# approg.net
KiCad netlist of a schematic drawn in EAGLE
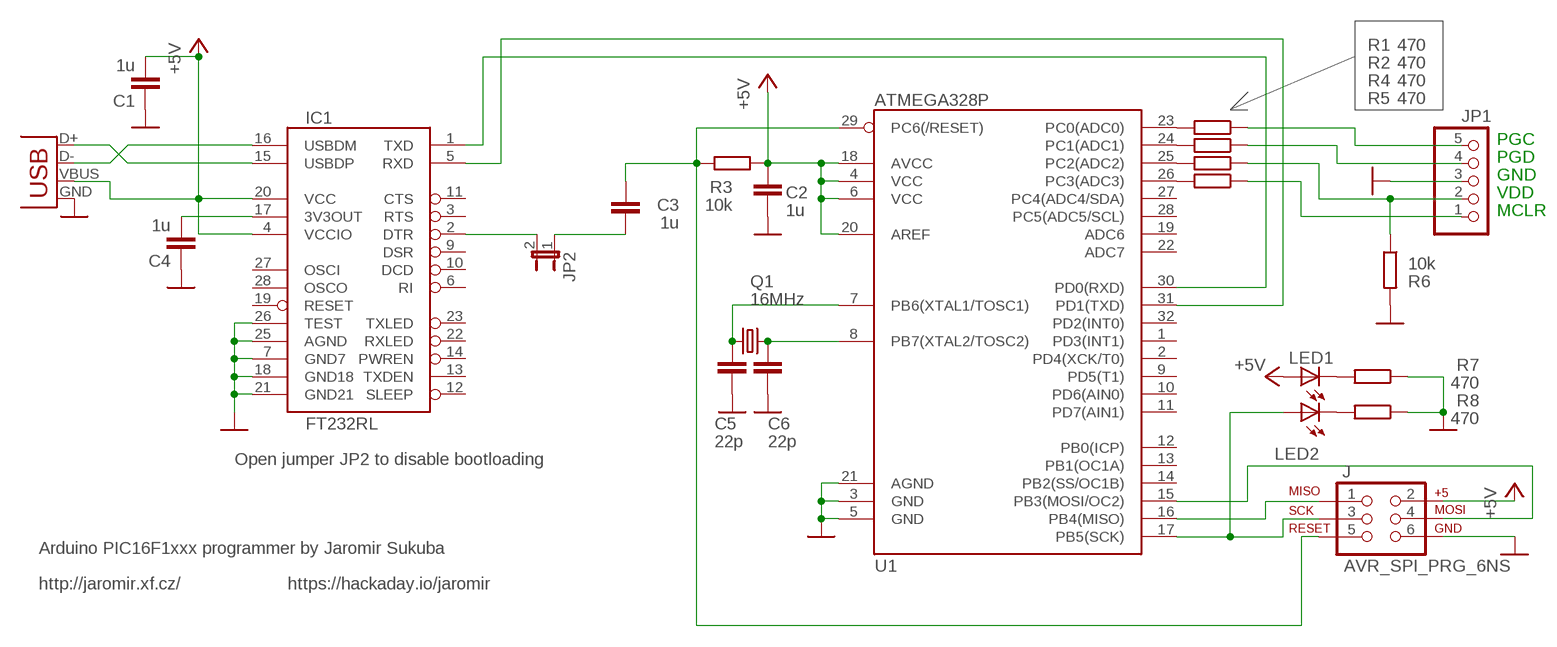
[diagram p0: schematic, sheet 1]

(export (version "E")
  (design (tool "Eeschema 10.0.6"))
  (components
    (comp (ref "C1")
      (value "1u")
      (footprint "eagle-import:R0805")
      (libsource (lib "eagle-import") (part "C_0806"))
    )
    (comp (ref "C2")
      (value "1u")
      (footprint "eagle-import:R0805")
      (libsource (lib "eagle-import") (part "C_0806"))
    )
    (comp (ref "C3")
      (value "1u")
      (footprint "eagle-import:R0805")
      (libsource (lib "eagle-import") (part "C_0806"))
    )
    (comp (ref "C4")
      (value "1u")
      (footprint "eagle-import:R0805")
      (libsource (lib "eagle-import") (part "C_0806"))
    )
    (comp (ref "C5")
      (value "22p")
      (footprint "eagle-import:R0805")
      (libsource (lib "eagle-import") (part "C_0806"))
    )
    (comp (ref "C6")
      (value "22p")
      (footprint "eagle-import:R0805")
      (libsource (lib "eagle-import") (part "C_0806"))
    )
    (comp (ref "IC1")
      (value "FT232RL")
      (footprint "eagle-import:SSOP28DB")
      (libsource (lib "eagle-import") (part "FT232RLSSOP"))
    )
    (comp (ref "J")
      (value "AVR_SPI_PRG_6NS")
      (footprint "eagle-import:2X3-NS")
      (libsource (lib "eagle-import") (part "AVR_SPI_PRG_6NS"))
    )
    (comp (ref "JP1")
      (value "PINHD-1X5/90")
      (footprint "eagle-import:1X05_90")
      (libsource (lib "eagle-import") (part "PINHD-1X5/90"))
    )
    (comp (ref "JP2")
      (value "JP1E")
      (footprint "eagle-import:JP1")
      (libsource (lib "eagle-import") (part "JP1E"))
    )
    (comp (ref "LED1")
      (value "LEDCHIPLED_0805")
      (footprint "eagle-import:CHIPLED_0805")
      (libsource (lib "eagle-import") (part "LEDCHIPLED_0805"))
    )
    (comp (ref "LED2")
      (value "LEDCHIPLED_0805")
      (footprint "eagle-import:CHIPLED_0805")
      (libsource (lib "eagle-import") (part "LEDCHIPLED_0805"))
    )
    (comp (ref "Q1")
      (value "16MHz")
      (footprint "eagle-import:HC49_S")
      (libsource (lib "eagle-import") (part "CRYSTALHC49S"))
    )
    (comp (ref "R1")
      (value "470")
      (footprint "eagle-import:R0805")
      (libsource (lib "eagle-import") (part "R_0805"))
    )
    (comp (ref "R2")
      (value "470")
      (footprint "eagle-import:R0805")
      (libsource (lib "eagle-import") (part "R_0805"))
    )
    (comp (ref "R3")
      (value "10k")
      (footprint "eagle-import:R0805")
      (libsource (lib "eagle-import") (part "R_0805"))
    )
    (comp (ref "R4")
      (value "470")
      (footprint "eagle-import:R0805")
      (libsource (lib "eagle-import") (part "R_0805"))
    )
    (comp (ref "R5")
      (value "470")
      (footprint "eagle-import:R0805")
      (libsource (lib "eagle-import") (part "R_0805"))
    )
    (comp (ref "R6")
      (value "10k")
      (footprint "eagle-import:R0805")
      (libsource (lib "eagle-import") (part "R_0805"))
    )
    (comp (ref "R7")
      (value "470")
      (footprint "eagle-import:R0805")
      (libsource (lib "eagle-import") (part "R_0805"))
    )
    (comp (ref "R8")
      (value "470")
      (footprint "eagle-import:R0805")
      (libsource (lib "eagle-import") (part "R_0805"))
    )
    (comp (ref "U1")
      (value "ATMEGA328P")
      (footprint "eagle-import:TQFP32-08")
      (libsource (lib "eagle-import") (part "ATMEGA328_SMT"))
    )
    (comp (ref "X1")
      (value "USB-MICROB")
      (footprint "eagle-import:USB-MICROB")
      (libsource (lib "eagle-import") (part "USB-MICROB"))
    )
  )
  (nets
    (net (code "1") (name "+5V") (class "Default")
      (node (ref "C1") (pin "2") (pinfunction "2_2") (pintype "passive"))
      (node (ref "C2") (pin "1") (pinfunction "1_1") (pintype "passive"))
      (node (ref "IC1") (pin "20") (pinfunction "VCC_20") (pintype "power_in"))
      (node (ref "IC1") (pin "4") (pinfunction "VCCIO_4") (pintype "power_in"))
      (node (ref "J") (pin "2") (pinfunction "2_2") (pintype "passive"))
      (node (ref "LED1") (pin "A") (pinfunction "A_A") (pintype "passive"))
      (node (ref "R3") (pin "1") (pinfunction "1_1") (pintype "passive"))
      (node (ref "U1") (pin "18") (pinfunction "AVCC_18") (pintype "bidirectional"))
      (node (ref "U1") (pin "20") (pinfunction "AREF_20") (pintype "bidirectional"))
      (node (ref "U1") (pin "4") (pinfunction "VCC_4") (pintype "bidirectional"))
      (node (ref "U1") (pin "6") (pinfunction "VCC_6") (pintype "bidirectional"))
      (node (ref "X1") (pin "VBUS") (pinfunction "VBUS_VBUS") (pintype "bidirectional"))
    )
    (net (code "2") (name "GND") (class "Default")
      (node (ref "C1") (pin "1") (pinfunction "1_1") (pintype "passive"))
      (node (ref "C2") (pin "2") (pinfunction "2_2") (pintype "passive"))
      (node (ref "C4") (pin "1") (pinfunction "1_1") (pintype "passive"))
      (node (ref "C5") (pin "2") (pinfunction "2_2") (pintype "passive"))
      (node (ref "C6") (pin "2") (pinfunction "2_2") (pintype "passive"))
      (node (ref "IC1") (pin "18") (pinfunction "GND18_18") (pintype "power_in"))
      (node (ref "IC1") (pin "21") (pinfunction "GND21_21") (pintype "power_in"))
      (node (ref "IC1") (pin "25") (pinfunction "AGND_25") (pintype "power_in"))
      (node (ref "IC1") (pin "26") (pinfunction "TEST_26") (pintype "input"))
      (node (ref "IC1") (pin "7") (pinfunction "GND7_7") (pintype "power_in"))
      (node (ref "J") (pin "6") (pinfunction "6_6") (pintype "passive"))
      (node (ref "JP1") (pin "3") (pinfunction "3_3") (pintype "passive"))
      (node (ref "R6") (pin "2") (pinfunction "2_2") (pintype "passive"))
      (node (ref "R7") (pin "1") (pinfunction "1_1") (pintype "passive"))
      (node (ref "R8") (pin "1") (pinfunction "1_1") (pintype "passive"))
      (node (ref "U1") (pin "21") (pinfunction "AGND_21") (pintype "bidirectional"))
      (node (ref "U1") (pin "3") (pinfunction "GND_3") (pintype "bidirectional"))
      (node (ref "U1") (pin "5") (pinfunction "GND_5") (pintype "bidirectional"))
      (node (ref "X1") (pin "GND") (pinfunction "GND_GND") (pintype "bidirectional"))
    )
    (net (code "3") (name "Net-(C3-Pad2)") (class "Default")
      (node (ref "C3") (pin "2") (pinfunction "2_2") (pintype "passive"))
      (node (ref "JP2") (pin "1") (pinfunction "1_1") (pintype "passive"))
    )
    (net (code "4") (name "Net-(IC1-3V3OUT)") (class "Default")
      (node (ref "C4") (pin "2") (pinfunction "2_2") (pintype "passive"))
      (node (ref "IC1") (pin "17") (pinfunction "3V3OUT_17") (pintype "output"))
    )
    (net (code "5") (name "Net-(IC1-DTR)") (class "Default")
      (node (ref "IC1") (pin "2") (pinfunction "DTR_2") (pintype "output"))
      (node (ref "JP2") (pin "2") (pinfunction "2_2") (pintype "passive"))
    )
    (net (code "6") (name "Net-(IC1-RXD)") (class "Default")
      (node (ref "IC1") (pin "5") (pinfunction "RXD_5") (pintype "input"))
      (node (ref "U1") (pin "31") (pinfunction "PD1(TXD)_31") (pintype "bidirectional"))
    )
    (net (code "7") (name "Net-(IC1-TXD)") (class "Default")
      (node (ref "IC1") (pin "1") (pinfunction "TXD_1") (pintype "output"))
      (node (ref "U1") (pin "30") (pinfunction "PD0(RXD)_30") (pintype "bidirectional"))
    )
    (net (code "8") (name "Net-(IC1-USBDM)") (class "Default")
      (node (ref "IC1") (pin "16") (pinfunction "USBDM_16") (pintype "bidirectional"))
      (node (ref "X1") (pin "D-") (pinfunction "D-_D-") (pintype "bidirectional"))
    )
    (net (code "9") (name "Net-(IC1-USBDP)") (class "Default")
      (node (ref "IC1") (pin "15") (pinfunction "USBDP_15") (pintype "bidirectional"))
      (node (ref "X1") (pin "D+") (pinfunction "D+_D+") (pintype "bidirectional"))
    )
    (net (code "10") (name "Net-(JP1-Pad1)") (class "Default")
      (node (ref "JP1") (pin "1") (pinfunction "1_1") (pintype "passive"))
      (node (ref "R5") (pin "1") (pinfunction "1_1") (pintype "passive"))
    )
    (net (code "11") (name "Net-(JP1-Pad2)") (class "Default")
      (node (ref "JP1") (pin "2") (pinfunction "2_2") (pintype "passive"))
      (node (ref "R4") (pin "1") (pinfunction "1_1") (pintype "passive"))
      (node (ref "R6") (pin "1") (pinfunction "1_1") (pintype "passive"))
    )
    (net (code "12") (name "Net-(JP1-Pad4)") (class "Default")
      (node (ref "JP1") (pin "4") (pinfunction "4_4") (pintype "passive"))
      (node (ref "R2") (pin "1") (pinfunction "1_1") (pintype "passive"))
    )
    (net (code "13") (name "Net-(JP1-Pad5)") (class "Default")
      (node (ref "JP1") (pin "5") (pinfunction "5_5") (pintype "passive"))
      (node (ref "R1") (pin "1") (pinfunction "1_1") (pintype "passive"))
    )
    (net (code "14") (name "Net-(LED1-PadC)") (class "Default")
      (node (ref "LED1") (pin "C") (pinfunction "C_C") (pintype "passive"))
      (node (ref "R7") (pin "2") (pinfunction "2_2") (pintype "passive"))
    )
    (net (code "15") (name "Net-(LED2-PadC)") (class "Default")
      (node (ref "LED2") (pin "C") (pinfunction "C_C") (pintype "passive"))
      (node (ref "R8") (pin "2") (pinfunction "2_2") (pintype "passive"))
    )
    (net (code "16") (name "Net-(U1-PB3(MOSI{slash}OC2))") (class "Default")
      (node (ref "J") (pin "4") (pinfunction "4_4") (pintype "passive"))
      (node (ref "U1") (pin "15") (pinfunction "PB3(MOSI/OC2)_15") (pintype "bidirectional"))
    )
    (net (code "17") (name "Net-(U1-PB4(MISO))") (class "Default")
      (node (ref "J") (pin "1") (pinfunction "1_1") (pintype "passive"))
      (node (ref "U1") (pin "16") (pinfunction "PB4(MISO)_16") (pintype "bidirectional"))
    )
    (net (code "18") (name "Net-(U1-PB5(SCK))") (class "Default")
      (node (ref "J") (pin "3") (pinfunction "3_3") (pintype "passive"))
      (node (ref "LED2") (pin "A") (pinfunction "A_A") (pintype "passive"))
      (node (ref "U1") (pin "17") (pinfunction "PB5(SCK)_17") (pintype "bidirectional"))
    )
    (net (code "19") (name "Net-(U1-PB6(XTAL1{slash}TOSC1))") (class "Default")
      (node (ref "C5") (pin "1") (pinfunction "1_1") (pintype "passive"))
      (node (ref "Q1") (pin "1") (pinfunction "1_1") (pintype "passive"))
      (node (ref "U1") (pin "7") (pinfunction "PB6(XTAL1/TOSC1)_7") (pintype "bidirectional"))
    )
    (net (code "20") (name "Net-(U1-PB7(XTAL2{slash}TOSC2))") (class "Default")
      (node (ref "C6") (pin "1") (pinfunction "1_1") (pintype "passive"))
      (node (ref "Q1") (pin "2") (pinfunction "2_2") (pintype "passive"))
      (node (ref "U1") (pin "8") (pinfunction "PB7(XTAL2/TOSC2)_8") (pintype "bidirectional"))
    )
    (net (code "21") (name "Net-(U1-PC0(ADC0))") (class "Default")
      (node (ref "R1") (pin "2") (pinfunction "2_2") (pintype "passive"))
      (node (ref "U1") (pin "23") (pinfunction "PC0(ADC0)_23") (pintype "bidirectional"))
    )
    (net (code "22") (name "Net-(U1-PC1(ADC1))") (class "Default")
      (node (ref "R2") (pin "2") (pinfunction "2_2") (pintype "passive"))
      (node (ref "U1") (pin "24") (pinfunction "PC1(ADC1)_24") (pintype "bidirectional"))
    )
    (net (code "23") (name "Net-(U1-PC2(ADC2))") (class "Default")
      (node (ref "R4") (pin "2") (pinfunction "2_2") (pintype "passive"))
      (node (ref "U1") (pin "25") (pinfunction "PC2(ADC2)_25") (pintype "bidirectional"))
    )
    (net (code "24") (name "Net-(U1-PC3(ADC3))") (class "Default")
      (node (ref "R5") (pin "2") (pinfunction "2_2") (pintype "passive"))
      (node (ref "U1") (pin "26") (pinfunction "PC3(ADC3)_26") (pintype "bidirectional"))
    )
    (net (code "25") (name "Net-(U1-PC6({slash}RESET))") (class "Default")
      (node (ref "C3") (pin "1") (pinfunction "1_1") (pintype "passive"))
      (node (ref "J") (pin "5") (pinfunction "5_5") (pintype "passive"))
      (node (ref "R3") (pin "2") (pinfunction "2_2") (pintype "passive"))
      (node (ref "U1") (pin "29") (pinfunction "PC6(/RESET)_29") (pintype "bidirectional"))
    )
    (net (code "26") (name "unconnected-(IC1-CTS-Pad11)") (class "Default")
      (node (ref "IC1") (pin "11") (pinfunction "CTS_11") (pintype "input"))
    )
    (net (code "27") (name "unconnected-(IC1-DCD-Pad10)") (class "Default")
      (node (ref "IC1") (pin "10") (pinfunction "DCD_10") (pintype "input"))
    )
    (net (code "28") (name "unconnected-(IC1-DSR-Pad9)") (class "Default")
      (node (ref "IC1") (pin "9") (pinfunction "DSR_9") (pintype "input"))
    )
    (net (code "29") (name "unconnected-(IC1-OSCI-Pad27)") (class "Default")
      (node (ref "IC1") (pin "27") (pinfunction "OSCI_27") (pintype "input"))
    )
    (net (code "30") (name "unconnected-(IC1-OSCO-Pad28)") (class "Default")
      (node (ref "IC1") (pin "28") (pinfunction "OSCO_28") (pintype "output"))
    )
    (net (code "31") (name "unconnected-(IC1-PWREN-Pad14)") (class "Default")
      (node (ref "IC1") (pin "14") (pinfunction "PWREN_14") (pintype "input"))
    )
    (net (code "32") (name "unconnected-(IC1-RESET-Pad19)") (class "Default")
      (node (ref "IC1") (pin "19") (pinfunction "RESET_19") (pintype "input"))
    )
    (net (code "33") (name "unconnected-(IC1-RI-Pad6)") (class "Default")
      (node (ref "IC1") (pin "6") (pinfunction "RI_6") (pintype "input"))
    )
    (net (code "34") (name "unconnected-(IC1-RTS-Pad3)") (class "Default")
      (node (ref "IC1") (pin "3") (pinfunction "RTS_3") (pintype "output"))
    )
    (net (code "35") (name "unconnected-(IC1-RXLED-Pad22)") (class "Default")
      (node (ref "IC1") (pin "22") (pinfunction "RXLED_22") (pintype "input"))
    )
    (net (code "36") (name "unconnected-(IC1-SLEEP-Pad12)") (class "Default")
      (node (ref "IC1") (pin "12") (pinfunction "SLEEP_12") (pintype "input"))
    )
    (net (code "37") (name "unconnected-(IC1-TXDEN-Pad13)") (class "Default")
      (node (ref "IC1") (pin "13") (pinfunction "TXDEN_13") (pintype "input"))
    )
    (net (code "38") (name "unconnected-(IC1-TXLED-Pad23)") (class "Default")
      (node (ref "IC1") (pin "23") (pinfunction "TXLED_23") (pintype "input"))
    )
    (net (code "39") (name "unconnected-(U1-ADC6-Pad19)") (class "Default")
      (node (ref "U1") (pin "19") (pinfunction "ADC6_19") (pintype "bidirectional"))
    )
    (net (code "40") (name "unconnected-(U1-ADC7-Pad22)") (class "Default")
      (node (ref "U1") (pin "22") (pinfunction "ADC7_22") (pintype "bidirectional"))
    )
    (net (code "41") (name "unconnected-(U1-PB0(ICP)-Pad12)") (class "Default")
      (node (ref "U1") (pin "12") (pinfunction "PB0(ICP)_12") (pintype "bidirectional"))
    )
    (net (code "42") (name "unconnected-(U1-PB1(OC1A)-Pad13)") (class "Default")
      (node (ref "U1") (pin "13") (pinfunction "PB1(OC1A)_13") (pintype "bidirectional"))
    )
    (net (code "43") (name "unconnected-(U1-PB2(SS{slash}OC1B)-Pad14)") (class "Default")
      (node (ref "U1") (pin "14") (pinfunction "PB2(SS/OC1B)_14") (pintype "bidirectional"))
    )
    (net (code "44") (name "unconnected-(U1-PC4(ADC4{slash}SDA)-Pad27)") (class "Default")
      (node (ref "U1") (pin "27") (pinfunction "PC4(ADC4/SDA)_27") (pintype "bidirectional"))
    )
    (net (code "45") (name "unconnected-(U1-PC5(ADC5{slash}SCL)-Pad28)") (class "Default")
      (node (ref "U1") (pin "28") (pinfunction "PC5(ADC5/SCL)_28") (pintype "bidirectional"))
    )
    (net (code "46") (name "unconnected-(U1-PD2(INT0)-Pad32)") (class "Default")
      (node (ref "U1") (pin "32") (pinfunction "PD2(INT0)_32") (pintype "bidirectional"))
    )
    (net (code "47") (name "unconnected-(U1-PD3(INT1)-Pad1)") (class "Default")
      (node (ref "U1") (pin "1") (pinfunction "PD3(INT1)_1") (pintype "bidirectional"))
    )
    (net (code "48") (name "unconnected-(U1-PD4(XCK{slash}T0)-Pad2)") (class "Default")
      (node (ref "U1") (pin "2") (pinfunction "PD4(XCK/T0)_2") (pintype "bidirectional"))
    )
    (net (code "49") (name "unconnected-(U1-PD5(T1)-Pad9)") (class "Default")
      (node (ref "U1") (pin "9") (pinfunction "PD5(T1)_9") (pintype "bidirectional"))
    )
    (net (code "50") (name "unconnected-(U1-PD6(AIN0)-Pad10)") (class "Default")
      (node (ref "U1") (pin "10") (pinfunction "PD6(AIN0)_10") (pintype "bidirectional"))
    )
    (net (code "51") (name "unconnected-(U1-PD7(AIN1)-Pad11)") (class "Default")
      (node (ref "U1") (pin "11") (pinfunction "PD7(AIN1)_11") (pintype "bidirectional"))
    )
  )
)
